# EE-SX1131.net
KiCad netlist of a schematic drawn in EAGLE
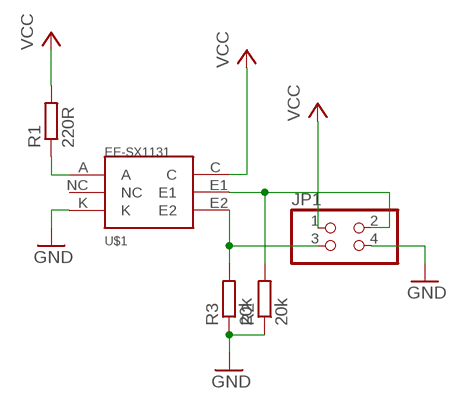
[diagram p0: schematic, sheet 1]

(export (version "E")
  (design (tool "Eeschema 10.0.6"))
  (components
    (comp (ref "JP1")
      (value "PINHD-2X2")
      (footprint "eagle-import:2X02")
      (libsource (lib "eagle-import") (part "PINHD-2X2"))
    )
    (comp (ref "R1")
      (value "220R")
      (footprint "eagle-import:M0805")
      (libsource (lib "eagle-import") (part "R-EU_M0805"))
    )
    (comp (ref "R2")
      (value "20k")
      (footprint "eagle-import:M0805")
      (libsource (lib "eagle-import") (part "R-EU_M0805"))
    )
    (comp (ref "R3")
      (value "20k")
      (footprint "eagle-import:M0805")
      (libsource (lib "eagle-import") (part "R-EU_M0805"))
    )
    (comp (ref "U$1")
      (value "EE-SX1131")
      (footprint "eagle-import:EE-SX1131")
      (libsource (lib "eagle-import") (part "EE-SX1131"))
    )
  )
  (nets
    (net (code "1") (name "GND") (class "Default")
      (node (ref "JP1") (pin "4") (pinfunction "4_4") (pintype "passive"))
      (node (ref "R2") (pin "1") (pinfunction "1_1") (pintype "passive"))
      (node (ref "R3") (pin "1") (pinfunction "1_1") (pintype "passive"))
      (node (ref "U$1") (pin "K") (pinfunction "K_K") (pintype "bidirectional"))
    )
    (net (code "2") (name "Net-(JP1-Pad2)") (class "Default")
      (node (ref "JP1") (pin "2") (pinfunction "2_2") (pintype "passive"))
      (node (ref "R2") (pin "2") (pinfunction "2_2") (pintype "passive"))
      (node (ref "U$1") (pin "E1") (pinfunction "E1_E1") (pintype "bidirectional"))
    )
    (net (code "3") (name "Net-(JP1-Pad3)") (class "Default")
      (node (ref "JP1") (pin "3") (pinfunction "3_3") (pintype "passive"))
      (node (ref "R3") (pin "2") (pinfunction "2_2") (pintype "passive"))
      (node (ref "U$1") (pin "E2") (pinfunction "E2_E2") (pintype "bidirectional"))
    )
    (net (code "4") (name "Net-(R1-Pad1)") (class "Default")
      (node (ref "R1") (pin "1") (pinfunction "1_1") (pintype "passive"))
      (node (ref "U$1") (pin "A") (pinfunction "A_A") (pintype "input"))
    )
    (net (code "5") (name "VCC") (class "Default")
      (node (ref "JP1") (pin "1") (pinfunction "1_1") (pintype "passive"))
      (node (ref "R1") (pin "2") (pinfunction "2_2") (pintype "passive"))
      (node (ref "U$1") (pin "C") (pinfunction "C_C") (pintype "bidirectional"))
    )
    (net (code "6") (name "unconnected-(U$1-PadNC)") (class "Default")
      (node (ref "U$1") (pin "NC") (pinfunction "NC_NC") (pintype "no_connect"))
    )
  )
)
